# Metro_M4_Express_AirLift.net
KiCad netlist of a schematic drawn in EAGLE
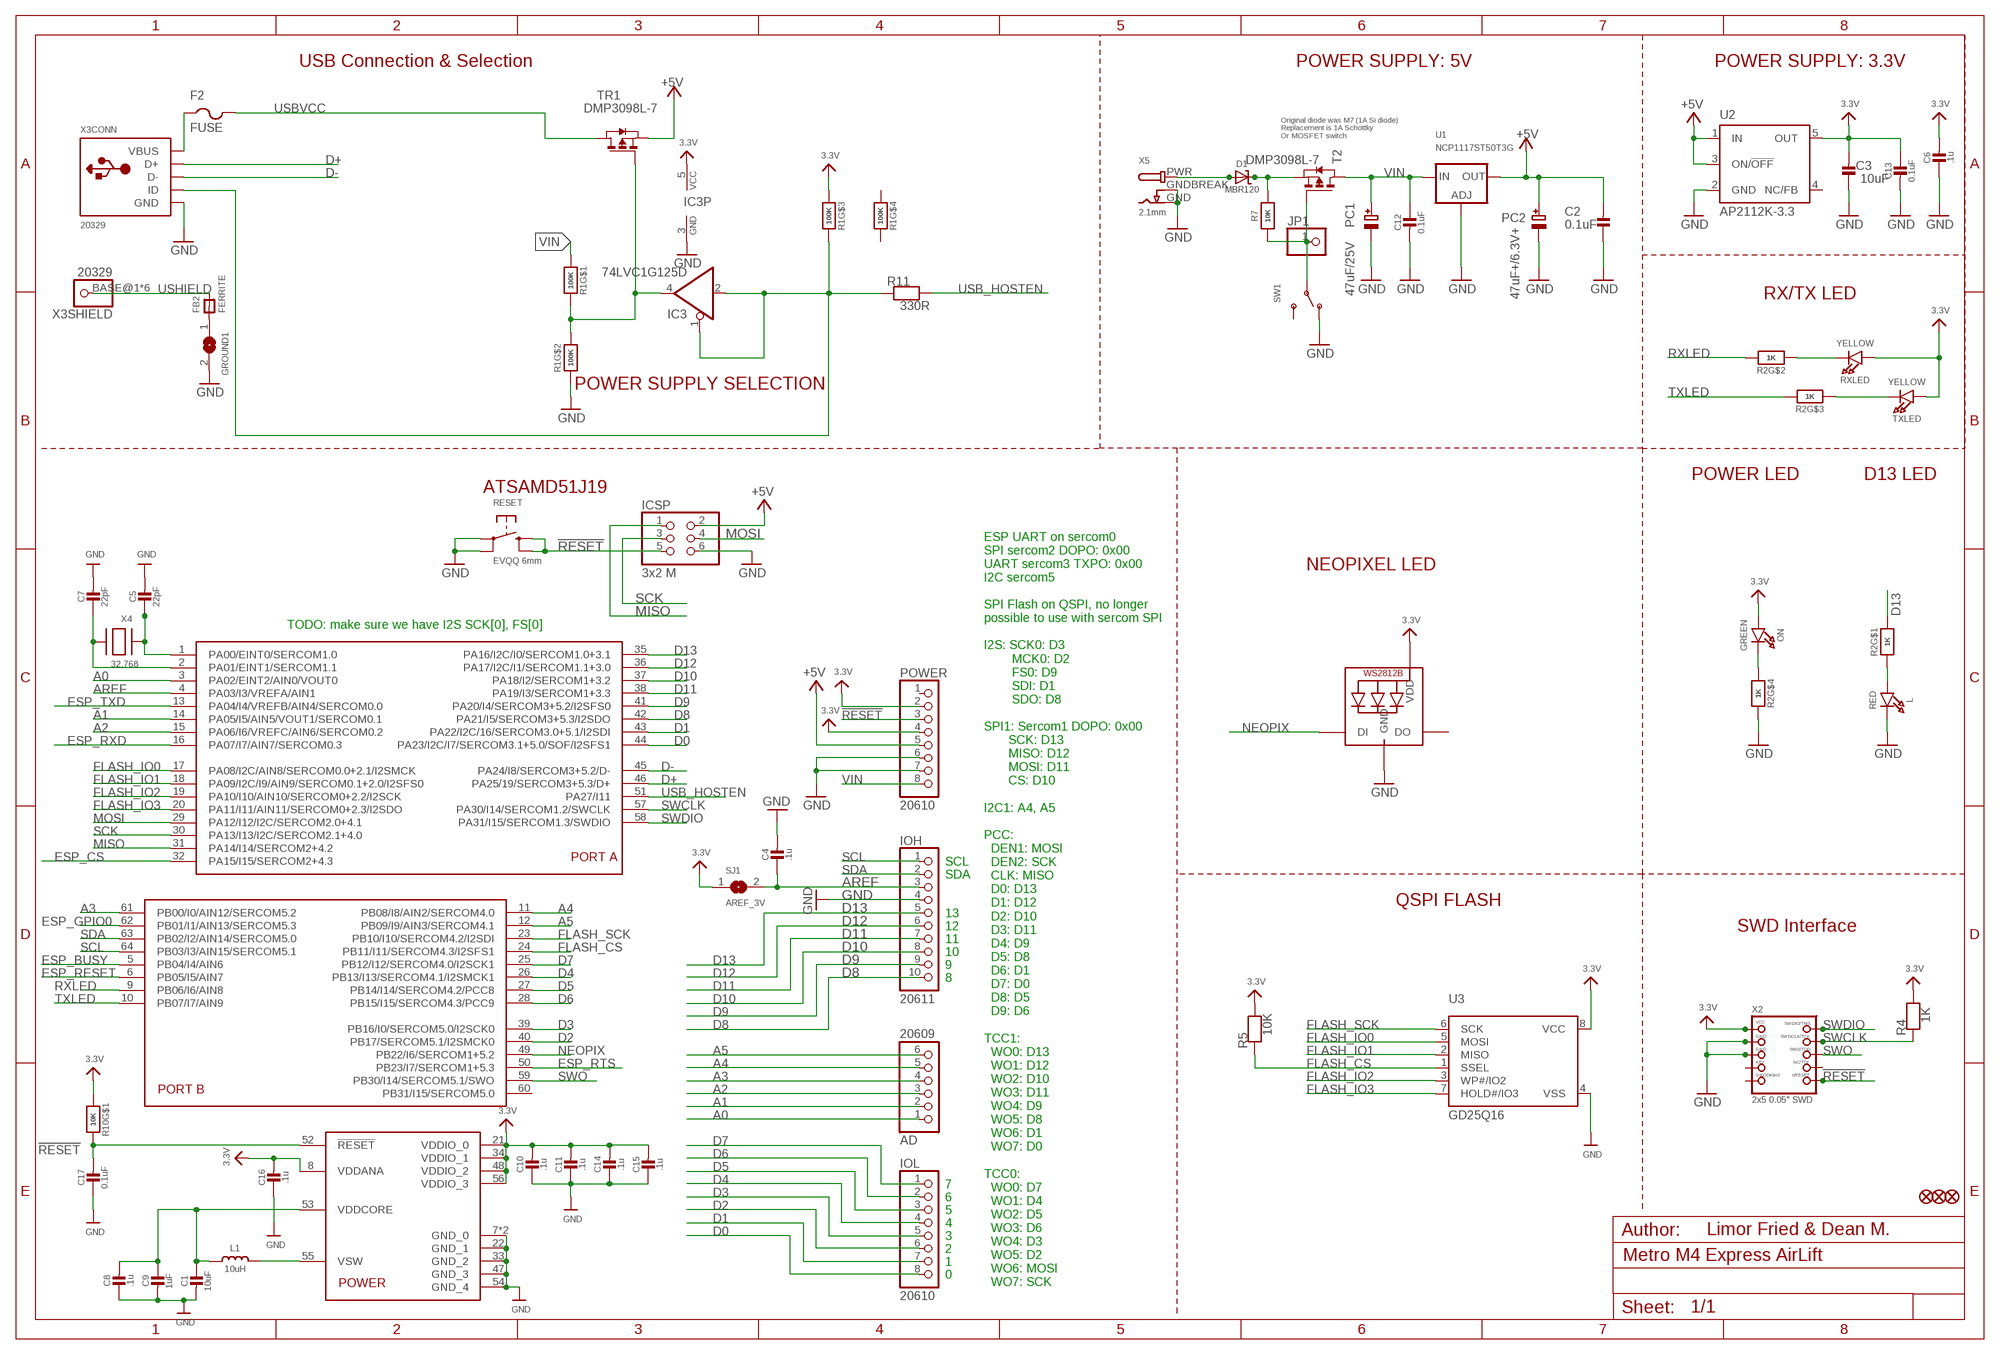
[diagram p0: schematic, sheet 1, part 1 of 2]
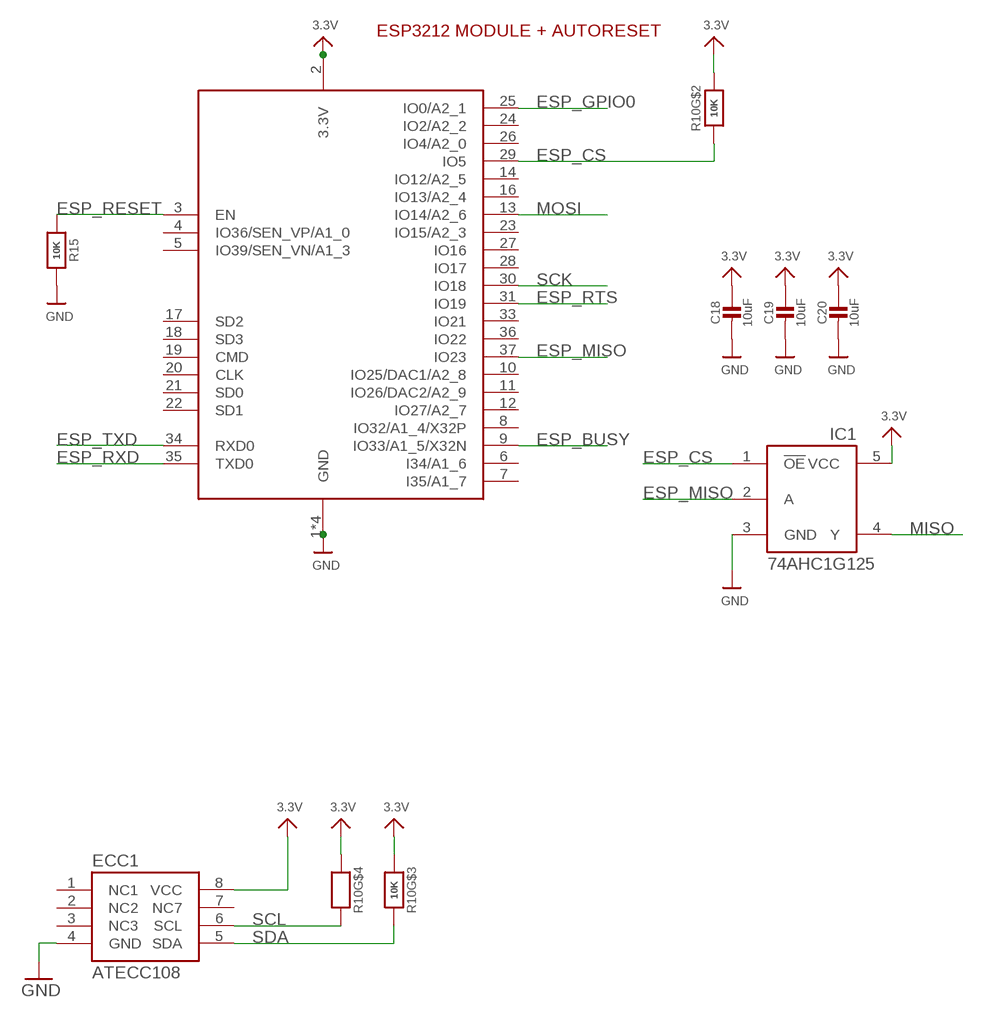
[diagram p1: schematic, sheet 1, part 2 of 2]

(export (version "E")
  (design (tool "Eeschema 10.0.6"))
  (components
    (comp (ref "AD")
      (value "20609")
      (footprint "eagle-import:1X06_OVALWAVE")
      (libsource (lib "eagle-import") (part "HEADER-1X6OVALWAVE"))
    )
    (comp (ref "C1")
      (value "10uF")
      (footprint "eagle-import:0805-NO")
      (libsource (lib "eagle-import") (part "CAP_CERAMIC0805-NOOUTLINE"))
    )
    (comp (ref "C2")
      (value "0.1uF")
      (footprint "eagle-import:0805-NO")
      (libsource (lib "eagle-import") (part "CAP_CERAMIC0805-NOOUTLINE"))
    )
    (comp (ref "C3")
      (value "10uF")
      (footprint "eagle-import:0805-NO")
      (libsource (lib "eagle-import") (part "CAP_CERAMIC0805-NOOUTLINE"))
    )
    (comp (ref "C4")
      (value ".1u")
      (footprint "eagle-import:0603-NO")
      (libsource (lib "eagle-import") (part "CAP_CERAMIC0603_NO"))
    )
    (comp (ref "C5")
      (value "22pF")
      (footprint "eagle-import:0603-NO")
      (libsource (lib "eagle-import") (part "CAP_CERAMIC0603_NO"))
    )
    (comp (ref "C6")
      (value ".1u")
      (footprint "eagle-import:0603-NO")
      (libsource (lib "eagle-import") (part "CAP_CERAMIC0603_NO"))
    )
    (comp (ref "C7")
      (value "22pF")
      (footprint "eagle-import:0603-NO")
      (libsource (lib "eagle-import") (part "CAP_CERAMIC0603_NO"))
    )
    (comp (ref "C8")
      (value ".1u")
      (footprint "eagle-import:0603-NO")
      (libsource (lib "eagle-import") (part "CAP_CERAMIC0603_NO"))
    )
    (comp (ref "C9")
      (value "1uF")
      (footprint "eagle-import:0603-NO")
      (libsource (lib "eagle-import") (part "CAP_CERAMIC0603_NO"))
    )
    (comp (ref "C10")
      (value ".1u")
      (footprint "eagle-import:0603-NO")
      (libsource (lib "eagle-import") (part "CAP_CERAMIC0603_NO"))
    )
    (comp (ref "C11")
      (value ".1u")
      (footprint "eagle-import:0603-NO")
      (libsource (lib "eagle-import") (part "CAP_CERAMIC0603_NO"))
    )
    (comp (ref "C12")
      (value "0.1uF")
      (footprint "eagle-import:0603-NO")
      (libsource (lib "eagle-import") (part "CAP_CERAMIC0603_NO"))
    )
    (comp (ref "C13")
      (value "0.1uF")
      (footprint "eagle-import:0603-NO")
      (libsource (lib "eagle-import") (part "CAP_CERAMIC0603_NO"))
    )
    (comp (ref "C14")
      (value ".1u")
      (footprint "eagle-import:0603-NO")
      (libsource (lib "eagle-import") (part "CAP_CERAMIC0603_NO"))
    )
    (comp (ref "C15")
      (value ".1u")
      (footprint "eagle-import:0603-NO")
      (libsource (lib "eagle-import") (part "CAP_CERAMIC0603_NO"))
    )
    (comp (ref "C16")
      (value ".1u")
      (footprint "eagle-import:0603-NO")
      (libsource (lib "eagle-import") (part "CAP_CERAMIC0603_NO"))
    )
    (comp (ref "C17")
      (value "0.1uF")
      (footprint "eagle-import:0603-NO")
      (libsource (lib "eagle-import") (part "CAP_CERAMIC0603_NO"))
    )
    (comp (ref "C18")
      (value "10uF")
      (footprint "eagle-import:0805-NO")
      (libsource (lib "eagle-import") (part "CAP_CERAMIC0805-NOOUTLINE"))
    )
    (comp (ref "C19")
      (value "10uF")
      (footprint "eagle-import:0805-NO")
      (libsource (lib "eagle-import") (part "CAP_CERAMIC0805-NOOUTLINE"))
    )
    (comp (ref "C20")
      (value "10uF")
      (footprint "eagle-import:0805-NO")
      (libsource (lib "eagle-import") (part "CAP_CERAMIC0805-NOOUTLINE"))
    )
    (comp (ref "D1")
      (value "MBR120")
      (footprint "eagle-import:SOD-123")
      (libsource (lib "eagle-import") (part "DIODE-SCHOTTKYSOD-123"))
    )
    (comp (ref "ECC1")
      (value "ATECC108")
      (footprint "eagle-import:SOIC8")
      (libsource (lib "eagle-import") (part "ATECC108"))
    )
    (comp (ref "F2")
      (value "FUSE")
      (footprint "eagle-import:R1206")
      (libsource (lib "eagle-import") (part "PTCFUSE-1206"))
    )
    (comp (ref "FB2")
      (value "FERRITE")
      (footprint "eagle-import:0805-NO")
      (libsource (lib "eagle-import") (part "FERRITE-0805NO"))
    )
    (comp (ref "FD1")
      (value "FIDUCIAL_1MM")
      (footprint "eagle-import:FIDUCIAL_1MM")
      (libsource (lib "eagle-import") (part "FIDUCIAL_1MM"))
    )
    (comp (ref "FD2")
      (value "FIDUCIAL_1MM")
      (footprint "eagle-import:FIDUCIAL_1MM")
      (libsource (lib "eagle-import") (part "FIDUCIAL_1MM"))
    )
    (comp (ref "FD3")
      (value "FIDUCIAL_1MM")
      (footprint "eagle-import:FIDUCIAL_1MM")
      (libsource (lib "eagle-import") (part "FIDUCIAL_1MM"))
    )
    (comp (ref "GROUND1")
      (value "SOLDERJUMPERCLOSED")
      (footprint "eagle-import:SOLDERJUMPER_CLOSEDWIRE")
      (libsource (lib "eagle-import") (part "SOLDERJUMPERCLOSED"))
    )
    (comp (ref "IC1")
      (value "74AHC1G125")
      (footprint "eagle-import:SOT23-5L")
      (libsource (lib "eagle-import") (part "74AHC1G125"))
    )
    (comp (ref "IC3")
      (value "74LVC1G125D")
      (footprint "eagle-import:SOT23-5")
      (libsource (lib "eagle-import") (part "741G125DBVAHC"))
    )
    (comp (ref "ICSP")
      (value "3x2 M")
      (footprint "eagle-import:2X03_ROUND_70MIL")
      (libsource (lib "eagle-import") (part "HEADER-2X3"))
    )
    (comp (ref "IOH")
      (value "20611")
      (footprint "eagle-import:1X10_OVALWAVE")
      (libsource (lib "eagle-import") (part "HEADER-1X10OVALWAVE"))
    )
    (comp (ref "IOL")
      (value "20610")
      (footprint "eagle-import:1X08_OVALWAVE")
      (libsource (lib "eagle-import") (part "HEADER-1X8OVALWAVE"))
    )
    (comp (ref "JP1")
      (value "HEADER-1X1ROUND")
      (footprint "eagle-import:1X01_ROUND")
      (libsource (lib "eagle-import") (part "HEADER-1X1ROUND"))
    )
    (comp (ref "L")
      (value "RED")
      (footprint "eagle-import:CHIPLED_0805_NOOUTLINE")
      (libsource (lib "eagle-import") (part "LED0805_NOOUTLINE"))
    )
    (comp (ref "L1")
      (value "10uH")
      (footprint "eagle-import:INDUCTOR_1007")
      (libsource (lib "eagle-import") (part "INDUCTOR"))
    )
    (comp (ref "LED1")
      (value "WS2812B3535")
      (footprint "eagle-import:LED3535")
      (libsource (lib "eagle-import") (part "WS2812B3535"))
    )
    (comp (ref "ON")
      (value "GREEN")
      (footprint "eagle-import:CHIPLED_0805_NOOUTLINE")
      (libsource (lib "eagle-import") (part "LED0805_NOOUTLINE"))
    )
    (comp (ref "PC1")
      (value "47uF/25V")
      (footprint "eagle-import:PANASONIC_D")
      (libsource (lib "eagle-import") (part "CAP_ELECTROLYTICPANASONIC_D"))
    )
    (comp (ref "PC2")
      (value "47uF+/6.3V+")
      (footprint "eagle-import:PANASONIC_D")
      (libsource (lib "eagle-import") (part "CAP_ELECTROLYTICPANASONIC_D"))
    )
    (comp (ref "POWER")
      (value "20610")
      (footprint "eagle-import:1X08_OVALWAVE")
      (libsource (lib "eagle-import") (part "HEADER-1X8OVALWAVE"))
    )
    (comp (ref "R1")
      (value "100K")
      (footprint "eagle-import:RESPACK_4X0603")
      (libsource (lib "eagle-import") (part "RESISTOR_4PACK"))
    )
    (comp (ref "R2")
      (value "1K")
      (footprint "eagle-import:RESPACK_4X0603")
      (libsource (lib "eagle-import") (part "RESISTOR_4PACK"))
    )
    (comp (ref "R4")
      (value "1K")
      (footprint "eagle-import:0603-NO")
      (libsource (lib "eagle-import") (part "RESISTOR_0603_NOOUT"))
    )
    (comp (ref "R5")
      (value "10K")
      (footprint "eagle-import:0603-NO")
      (libsource (lib "eagle-import") (part "RESISTOR_0603_NOOUT"))
    )
    (comp (ref "R7")
      (value "10K")
      (footprint "eagle-import:0603-NO")
      (libsource (lib "eagle-import") (part "RESISTOR_0603_NOOUT"))
    )
    (comp (ref "R10")
      (value "10K")
      (footprint "eagle-import:RESPACK_4X0603")
      (libsource (lib "eagle-import") (part "RESISTOR_4PACK"))
    )
    (comp (ref "R11")
      (value "330R")
      (footprint "eagle-import:0603-NO")
      (libsource (lib "eagle-import") (part "RESISTOR_0603_NOOUT"))
    )
    (comp (ref "R15")
      (value "10K")
      (footprint "eagle-import:0603-NO")
      (libsource (lib "eagle-import") (part "RESISTOR_0603_NOOUT"))
    )
    (comp (ref "RESET")
      (value "EVQQ 6mm")
      (footprint "eagle-import:EVQ-Q2_SMALLER")
      (libsource (lib "eagle-import") (part "SWITCH_TACT_SMT_EVQQ2_SMALL"))
    )
    (comp (ref "RXLED")
      (value "YELLOW")
      (footprint "eagle-import:CHIPLED_0805_NOOUTLINE")
      (libsource (lib "eagle-import") (part "LED0805_NOOUTLINE"))
    )
    (comp (ref "SJ1")
      (value "AREF_3V")
      (footprint "eagle-import:SOLDERJUMPER_CLOSEDWIRE")
      (libsource (lib "eagle-import") (part "SOLDERJUMPERCLOSED"))
    )
    (comp (ref "SW1")
      (value "SWITCH_SPDT")
      (footprint "eagle-import:SPDT_SMT_SSSS811101")
      (libsource (lib "eagle-import") (part "SWITCH_SPDT"))
    )
    (comp (ref "T2")
      (value "DMP3098L-7")
      (footprint "eagle-import:SOT-23")
      (libsource (lib "eagle-import") (part "PMOSSOT23"))
    )
    (comp (ref "TR1")
      (value "DMP3098L-7")
      (footprint "eagle-import:SOT-23")
      (fields (field (name "PART_NUMBER") "PMV48XP"))
      (libsource (lib "eagle-import") (part "0297_PMV48XP"))
    )
    (comp (ref "TXLED")
      (value "YELLOW")
      (footprint "eagle-import:CHIPLED_0805_NOOUTLINE")
      (libsource (lib "eagle-import") (part "LED0805_NOOUTLINE"))
    )
    (comp (ref "U$1")
      (value "ATSAMD51J19")
      (footprint "eagle-import:PQFN64-1")
      (libsource (lib "eagle-import") (part "ATSAMD51J"))
    )
    (comp (ref "U1")
      (value "NCP1117ST50T3G")
      (footprint "eagle-import:SOT223-R")
      (libsource (lib "eagle-import") (part "LM1117SOT223-REFLOW"))
    )
    (comp (ref "U2")
      (value "AP2112K-3.3")
      (footprint "eagle-import:SOT23-DBV")
      (libsource (lib "eagle-import") (part "LP2985-XXDBVR33"))
    )
    (comp (ref "U3")
      (value "GD25Q16")
      (footprint "eagle-import:SOIC8_208MIL")
      (libsource (lib "eagle-import") (part "SPIFLASH_8PIN208MIL"))
    )
    (comp (ref "X2")
      (value "2x5 0.05\" SWD")
      (footprint "eagle-import:2X05_1.27MM_BOX_POSTS")
      (libsource (lib "eagle-import") (part "JTAG-CORTEXBOXPOSTS"))
    )
    (comp (ref "X3")
      (value "20329")
      (footprint "eagle-import:4UCONN_20329_V2")
      (libsource (lib "eagle-import") (part "USB_W_SHIELD_V2"))
    )
    (comp (ref "X4")
      (value "32.768")
      (footprint "eagle-import:XTAL3215")
      (libsource (lib "eagle-import") (part "XTAL-3.2X1.5"))
    )
    (comp (ref "X5")
      (value "2.1mm")
      (footprint "eagle-import:DCJACK_2MM_PTH")
      (libsource (lib "eagle-import") (part "DCBARRELPTH"))
    )
    (comp (ref "X6")
      (value "ESP32_WROOM32")
      (footprint "eagle-import:WROOM32")
      (libsource (lib "eagle-import") (part "ESP32_WROOM32"))
    )
  )
  (nets
    (net (code "1") (name "+5V") (class "Default")
      (node (ref "C2") (pin "2") (pinfunction "2_2") (pintype "passive"))
      (node (ref "ICSP") (pin "2") (pinfunction "2_2") (pintype "passive"))
      (node (ref "PC2") (pin "+") (pinfunction "+_+") (pintype "passive"))
      (node (ref "POWER") (pin "5") (pinfunction "5_5") (pintype "passive"))
      (node (ref "TR1") (pin "2") (pinfunction "S_2") (pintype "passive"))
      (node (ref "U1") (pin "2") (pinfunction "OUT_2") (pintype "passive"))
      (node (ref "U1") (pin "4") (pinfunction "OUT_4") (pintype "passive"))
      (node (ref "U2") (pin "1") (pinfunction "IN_1") (pintype "input"))
      (node (ref "U2") (pin "3") (pinfunction "ON/~{OFF}_3") (pintype "input"))
    )
    (net (code "2") (name "/A0") (class "Default")
      (node (ref "AD") (pin "1") (pinfunction "1_1") (pintype "passive"))
      (node (ref "U$1") (pin "3") (pinfunction "PA02/EINT2/AIN0/VOUT0_3") (pintype "bidirectional"))
    )
    (net (code "3") (name "/A1") (class "Default")
      (node (ref "AD") (pin "2") (pinfunction "2_2") (pintype "passive"))
      (node (ref "U$1") (pin "14") (pinfunction "PA05/I5/AIN5/VOUT1/SERCOM0.1_14") (pintype "bidirectional"))
    )
    (net (code "4") (name "/A2") (class "Default")
      (node (ref "AD") (pin "3") (pinfunction "3_3") (pintype "passive"))
      (node (ref "U$1") (pin "15") (pinfunction "PA06/I6/VREFC/AIN6/SERCOM0.2_15") (pintype "bidirectional"))
    )
    (net (code "5") (name "/A3") (class "Default")
      (node (ref "AD") (pin "4") (pinfunction "4_4") (pintype "passive"))
      (node (ref "U$1") (pin "61") (pinfunction "PB00/I0/AIN12/SERCOM5.2_61") (pintype "bidirectional"))
    )
    (net (code "6") (name "/A4") (class "Default")
      (node (ref "AD") (pin "5") (pinfunction "5_5") (pintype "passive"))
      (node (ref "U$1") (pin "11") (pinfunction "PB08/I8/AIN2/SERCOM4.0_11") (pintype "bidirectional"))
    )
    (net (code "7") (name "/A5") (class "Default")
      (node (ref "AD") (pin "6") (pinfunction "6_6") (pintype "passive"))
      (node (ref "U$1") (pin "12") (pinfunction "PB09/I9/AIN3/SERCOM4.1_12") (pintype "bidirectional"))
    )
    (net (code "8") (name "/AREF") (class "Default")
      (node (ref "C4") (pin "1") (pinfunction "1_1") (pintype "passive"))
      (node (ref "IOH") (pin "3") (pinfunction "3_3") (pintype "passive"))
      (node (ref "SJ1") (pin "2") (pinfunction "2_2") (pintype "passive"))
      (node (ref "U$1") (pin "4") (pinfunction "PA03/I3/VREFA/AIN1_4") (pintype "bidirectional"))
    )
    (net (code "9") (name "/D+") (class "Default")
      (node (ref "U$1") (pin "46") (pinfunction "PA25/19/SERCOM3+5.3/D+_46") (pintype "bidirectional"))
      (node (ref "X3") (pin "D+") (pinfunction "D+_D+") (pintype "bidirectional"))
    )
    (net (code "10") (name "/D-") (class "Default")
      (node (ref "U$1") (pin "45") (pinfunction "PA24/I8/SERCOM3+5.2/D-_45") (pintype "bidirectional"))
      (node (ref "X3") (pin "D-") (pinfunction "D-_D-") (pintype "bidirectional"))
    )
    (net (code "11") (name "/D0") (class "Default")
      (node (ref "IOL") (pin "8") (pinfunction "8_8") (pintype "passive"))
      (node (ref "U$1") (pin "44") (pinfunction "PA23/I2C/I7/SERCOM3.1+5.0/SOF/I2SFS1_44") (pintype "bidirectional"))
    )
    (net (code "12") (name "/D1") (class "Default")
      (node (ref "IOL") (pin "7") (pinfunction "7_7") (pintype "passive"))
      (node (ref "U$1") (pin "43") (pinfunction "PA22/I2C/16/SERCOM3.0+5.1/I2SDI_43") (pintype "bidirectional"))
    )
    (net (code "13") (name "/D2") (class "Default")
      (node (ref "IOL") (pin "6") (pinfunction "6_6") (pintype "passive"))
      (node (ref "U$1") (pin "40") (pinfunction "PB17/SERCOM5.1/I2SMCK0_40") (pintype "bidirectional"))
    )
    (net (code "14") (name "/D3") (class "Default")
      (node (ref "IOL") (pin "5") (pinfunction "5_5") (pintype "passive"))
      (node (ref "U$1") (pin "39") (pinfunction "PB16/I0/SERCOM5.0/I2SCK0_39") (pintype "bidirectional"))
    )
    (net (code "15") (name "/D4") (class "Default")
      (node (ref "IOL") (pin "4") (pinfunction "4_4") (pintype "passive"))
      (node (ref "U$1") (pin "26") (pinfunction "PB13/I13/SERCOM4.1/I2SMCK1_26") (pintype "bidirectional"))
    )
    (net (code "16") (name "/D5") (class "Default")
      (node (ref "IOL") (pin "3") (pinfunction "3_3") (pintype "passive"))
      (node (ref "U$1") (pin "27") (pinfunction "PB14/I14/SERCOM4.2/PCC8_27") (pintype "bidirectional"))
    )
    (net (code "17") (name "/D6") (class "Default")
      (node (ref "IOL") (pin "2") (pinfunction "2_2") (pintype "passive"))
      (node (ref "U$1") (pin "28") (pinfunction "PB15/I15/SERCOM4.3/PCC9_28") (pintype "bidirectional"))
    )
    (net (code "18") (name "/D7") (class "Default")
      (node (ref "IOL") (pin "1") (pinfunction "1_1") (pintype "passive"))
      (node (ref "U$1") (pin "25") (pinfunction "PB12/I12/SERCOM4.0/I2SCK1_25") (pintype "bidirectional"))
    )
    (net (code "19") (name "/D8") (class "Default")
      (node (ref "IOH") (pin "10") (pinfunction "10_10") (pintype "passive"))
      (node (ref "U$1") (pin "42") (pinfunction "PA21/I5/SERCOM3+5.3/I2SDO_42") (pintype "bidirectional"))
    )
    (net (code "20") (name "/D9") (class "Default")
      (node (ref "IOH") (pin "9") (pinfunction "9_9") (pintype "passive"))
      (node (ref "U$1") (pin "41") (pinfunction "PA20/I4/SERCOM3+5.2/I2SFS0_41") (pintype "bidirectional"))
    )
    (net (code "21") (name "/D10") (class "Default")
      (node (ref "IOH") (pin "8") (pinfunction "8_8") (pintype "passive"))
      (node (ref "U$1") (pin "37") (pinfunction "PA18/I2/SERCOM1+3.2_37") (pintype "bidirectional"))
    )
    (net (code "22") (name "/D11") (class "Default")
      (node (ref "IOH") (pin "7") (pinfunction "7_7") (pintype "passive"))
      (node (ref "U$1") (pin "38") (pinfunction "PA19/I3/SERCOM1+3.3_38") (pintype "bidirectional"))
    )
    (net (code "23") (name "/D12") (class "Default")
      (node (ref "IOH") (pin "6") (pinfunction "6_6") (pintype "passive"))
      (node (ref "U$1") (pin "36") (pinfunction "PA17/I2C/I1/SERCOM1.1+3.0_36") (pintype "bidirectional"))
    )
    (net (code "24") (name "/D13") (class "Default")
      (node (ref "IOH") (pin "5") (pinfunction "5_5") (pintype "passive"))
      (node (ref "R2") (pin "8") (pinfunction "2_8") (pintype "passive"))
      (node (ref "U$1") (pin "35") (pinfunction "PA16/I2C/I0/SERCOM1.0+3.1_35") (pintype "bidirectional"))
    )
    (net (code "25") (name "/ESP_BUSY") (class "Default")
      (node (ref "U$1") (pin "5") (pinfunction "PB04/I4/AIN6_5") (pintype "bidirectional"))
      (node (ref "X6") (pin "9") (pinfunction "IO33/A1_5/X32N_9") (pintype "bidirectional"))
    )
    (net (code "26") (name "/ESP_CS") (class "Default")
      (node (ref "IC1") (pin "1") (pinfunction "~{OE}_1") (pintype "input"))
      (node (ref "R10") (pin "2") (pinfunction "1_2") (pintype "passive"))
      (node (ref "U$1") (pin "32") (pinfunction "PA15/I15/SERCOM2+4.3_32") (pintype "bidirectional"))
      (node (ref "X6") (pin "29") (pinfunction "IO5_29") (pintype "bidirectional"))
    )
    (net (code "27") (name "/ESP_GPIO0") (class "Default")
      (node (ref "U$1") (pin "62") (pinfunction "PB01/I1/AIN13/SERCOM5.3_62") (pintype "bidirectional"))
      (node (ref "X6") (pin "25") (pinfunction "IO0/A2_1_25") (pintype "bidirectional"))
    )
    (net (code "28") (name "/ESP_MISO") (class "Default")
      (node (ref "IC1") (pin "2") (pinfunction "A_2") (pintype "input"))
      (node (ref "X6") (pin "37") (pinfunction "IO23_37") (pintype "bidirectional"))
    )
    (net (code "29") (name "/ESP_RESET") (class "Default")
      (node (ref "R15") (pin "1") (pinfunction "1_1") (pintype "passive"))
      (node (ref "U$1") (pin "6") (pinfunction "PB05/I5/AIN7_6") (pintype "bidirectional"))
      (node (ref "X6") (pin "3") (pinfunction "EN_3") (pintype "input"))
    )
    (net (code "30") (name "/ESP_RTS") (class "Default")
      (node (ref "U$1") (pin "50") (pinfunction "PB23/I7/SERCOM1+5.3_50") (pintype "bidirectional"))
      (node (ref "X6") (pin "31") (pinfunction "IO19_31") (pintype "bidirectional"))
    )
    (net (code "31") (name "/ESP_RXD") (class "Default")
      (node (ref "U$1") (pin "16") (pinfunction "PA07/I7/AIN7/SERCOM0.3_16") (pintype "bidirectional"))
      (node (ref "X6") (pin "35") (pinfunction "TXD0_35") (pintype "output"))
    )
    (net (code "32") (name "/ESP_TXD") (class "Default")
      (node (ref "U$1") (pin "13") (pinfunction "PA04/I4/VREFB/AIN4/SERCOM0.0_13") (pintype "bidirectional"))
      (node (ref "X6") (pin "34") (pinfunction "RXD0_34") (pintype "input"))
    )
    (net (code "33") (name "/FLASH_CS") (class "Default")
      (node (ref "R5") (pin "1") (pinfunction "1_1") (pintype "passive"))
      (node (ref "U$1") (pin "24") (pinfunction "PB11/I11/SERCOM4.3/I2SFS1_24") (pintype "bidirectional"))
      (node (ref "U3") (pin "1") (pinfunction "SSEL_1") (pintype "bidirectional"))
    )
    (net (code "34") (name "/FLASH_IO0") (class "Default")
      (node (ref "U$1") (pin "17") (pinfunction "PA08/I2C/AIN8/SERCOM0.0+2.1/I2SMCK_17") (pintype "bidirectional"))
      (node (ref "U3") (pin "5") (pinfunction "MOSI_5") (pintype "bidirectional"))
    )
    (net (code "35") (name "/FLASH_IO1") (class "Default")
      (node (ref "U$1") (pin "18") (pinfunction "PA09/I2C/I9/AIN9/SERCOM0.1+2.0/I2SFS0_18") (pintype "bidirectional"))
      (node (ref "U3") (pin "2") (pinfunction "MISO_2") (pintype "bidirectional"))
    )
    (net (code "36") (name "/FLASH_IO2") (class "Default")
      (node (ref "U$1") (pin "19") (pinfunction "PA10/I10/AIN10/SERCOM0+2.2/I2SCK_19") (pintype "bidirectional"))
      (node (ref "U3") (pin "3") (pinfunction "WP#/IO2_3") (pintype "bidirectional"))
    )
    (net (code "37") (name "/FLASH_IO3") (class "Default")
      (node (ref "U$1") (pin "20") (pinfunction "PA11/I11/AIN11/SERCOM0+2.3/I2SDO_20") (pintype "bidirectional"))
      (node (ref "U3") (pin "7") (pinfunction "HOLD#/IO3_7") (pintype "bidirectional"))
    )
    (net (code "38") (name "/FLASH_SCK") (class "Default")
      (node (ref "U$1") (pin "23") (pinfunction "PB10/I10/SERCOM4.2/I2SDI_23") (pintype "bidirectional"))
      (node (ref "U3") (pin "6") (pinfunction "SCK_6") (pintype "bidirectional"))
    )
    (net (code "39") (name "/MISO") (class "Default")
      (node (ref "IC1") (pin "4") (pinfunction "Y_4") (pintype "output"))
      (node (ref "ICSP") (pin "1") (pinfunction "1_1") (pintype "passive"))
      (node (ref "U$1") (pin "31") (pinfunction "PA14/I14/SERCOM2+4.2_31") (pintype "bidirectional"))
    )
    (net (code "40") (name "/MOSI") (class "Default")
      (node (ref "ICSP") (pin "4") (pinfunction "4_4") (pintype "passive"))
      (node (ref "U$1") (pin "29") (pinfunction "PA12/I12/I2C/SERCOM2.0+4.1_29") (pintype "bidirectional"))
      (node (ref "X6") (pin "13") (pinfunction "IO14/A2_6_13") (pintype "bidirectional"))
    )
    (net (code "41") (name "/NEOPIX") (class "Default")
      (node (ref "LED1") (pin "1") (pinfunction "DI_1") (pintype "input"))
      (node (ref "U$1") (pin "49") (pinfunction "PB22/I6/SERCOM1+5.2_49") (pintype "bidirectional"))
    )
    (net (code "42") (name "/RXLED") (class "Default")
      (node (ref "R2") (pin "7") (pinfunction "2_7") (pintype "passive"))
      (node (ref "U$1") (pin "9") (pinfunction "PB06/I6/AIN8_9") (pintype "bidirectional"))
    )
    (net (code "43") (name "/SCK") (class "Default")
      (node (ref "ICSP") (pin "3") (pinfunction "3_3") (pintype "passive"))
      (node (ref "U$1") (pin "30") (pinfunction "PA13/I13/I2C/SERCOM2.1+4.0_30") (pintype "bidirectional"))
      (node (ref "X6") (pin "30") (pinfunction "IO18_30") (pintype "bidirectional"))
    )
    (net (code "44") (name "/SCL") (class "Default")
      (node (ref "ECC1") (pin "6") (pinfunction "SCL_6") (pintype "bidirectional"))
      (node (ref "IOH") (pin "1") (pinfunction "1_1") (pintype "passive"))
      (node (ref "R10") (pin "5") (pinfunction "2_5") (pintype "passive"))
      (node (ref "U$1") (pin "64") (pinfunction "PB03/I3/AIN15/SERCOM5.1_64") (pintype "bidirectional"))
    )
    (net (code "45") (name "/SDA") (class "Default")
      (node (ref "ECC1") (pin "5") (pinfunction "SDA_5") (pintype "bidirectional"))
      (node (ref "IOH") (pin "2") (pinfunction "2_2") (pintype "passive"))
      (node (ref "R10") (pin "6") (pinfunction "2_6") (pintype "passive"))
      (node (ref "U$1") (pin "63") (pinfunction "PB02/I2/AIN14/SERCOM5.0_63") (pintype "bidirectional"))
    )
    (net (code "46") (name "/SWCLK") (class "Default")
      (node (ref "R4") (pin "1") (pinfunction "1_1") (pintype "passive"))
      (node (ref "U$1") (pin "57") (pinfunction "PA30/I14/SERCOM1.2/SWCLK_57") (pintype "bidirectional"))
      (node (ref "X2") (pin "4") (pinfunction "SWDCLK_4") (pintype "bidirectional"))
    )
    (net (code "47") (name "/SWDIO") (class "Default")
      (node (ref "U$1") (pin "58") (pinfunction "PA31/I15/SERCOM1.3/SWDIO_58") (pintype "bidirectional"))
      (node (ref "X2") (pin "2") (pinfunction "SWDIO_2") (pintype "bidirectional"))
    )
    (net (code "48") (name "/SWO") (class "Default")
      (node (ref "U$1") (pin "59") (pinfunction "PB30/I14/SERCOM5.1/SWO_59") (pintype "bidirectional"))
      (node (ref "X2") (pin "6") (pinfunction "SWO_6") (pintype "bidirectional"))
    )
    (net (code "49") (name "/TXLED") (class "Default")
      (node (ref "R2") (pin "6") (pinfunction "2_6") (pintype "passive"))
      (node (ref "U$1") (pin "10") (pinfunction "PB07/I7/AIN9_10") (pintype "bidirectional"))
    )
    (net (code "50") (name "/USBVCC") (class "Default")
      (node (ref "F2") (pin "2") (pinfunction "2_2") (pintype "passive"))
      (node (ref "TR1") (pin "1") (pinfunction "D_1") (pintype "passive"))
    )
    (net (code "51") (name "/USB_HOSTEN") (class "Default")
      (node (ref "R11") (pin "2") (pinfunction "2_2") (pintype "passive"))
      (node (ref "U$1") (pin "51") (pinfunction "PA27/I11_51") (pintype "bidirectional"))
    )
    (net (code "52") (name "/USHIELD") (class "Default")
      (node (ref "FB2") (pin "2") (pinfunction "P$2_2") (pintype "passive"))
      (node (ref "X3") (pin "BASE@1") (pinfunction "1_BASE@1") (pintype "passive"))
      (node (ref "X3") (pin "BASE@2") (pinfunction "1_BASE@2") (pintype "passive"))
      (node (ref "X3") (pin "SPRT@1") (pinfunction "1_SPRT@1") (pintype "passive"))
      (node (ref "X3") (pin "SPRT@2") (pinfunction "1_SPRT@2") (pintype "passive"))
      (node (ref "X3") (pin "SPRT@3") (pinfunction "1_SPRT@3") (pintype "passive"))
      (node (ref "X3") (pin "SPRT@4") (pinfunction "1_SPRT@4") (pintype "passive"))
    )
    (net (code "53") (name "/~{RESET}") (class "Default")
      (node (ref "C17") (pin "2") (pinfunction "2_2") (pintype "passive"))
      (node (ref "ICSP") (pin "5") (pinfunction "5_5") (pintype "passive"))
      (node (ref "POWER") (pin "3") (pinfunction "3_3") (pintype "passive"))
      (node (ref "R10") (pin "8") (pinfunction "2_8") (pintype "passive"))
      (node (ref "RESET") (pin "B") (pinfunction "S_B") (pintype "passive"))
      (node (ref "RESET") (pin "B'") (pinfunction "S1_B'") (pintype "passive"))
      (node (ref "U$1") (pin "52") (pinfunction "~{RESET}_52") (pintype "bidirectional"))
      (node (ref "X2") (pin "10") (pinfunction "NRESET_10") (pintype "bidirectional"))
    )
    (net (code "54") (name "3.3V") (class "Default")
      (node (ref "C10") (pin "2") (pinfunction "2_2") (pintype "passive"))
      (node (ref "C11") (pin "2") (pinfunction "2_2") (pintype "passive"))
      (node (ref "C13") (pin "1") (pinfunction "1_1") (pintype "passive"))
      (node (ref "C14") (pin "2") (pinfunction "2_2") (pintype "passive"))
      (node (ref "C15") (pin "2") (pinfunction "2_2") (pintype "passive"))
      (node (ref "C16") (pin "2") (pinfunction "2_2") (pintype "passive"))
      (node (ref "C18") (pin "1") (pinfunction "1_1") (pintype "passive"))
      (node (ref "C19") (pin "1") (pinfunction "1_1") (pintype "passive"))
      (node (ref "C20") (pin "1") (pinfunction "1_1") (pintype "passive"))
      (node (ref "C3") (pin "2") (pinfunction "2_2") (pintype "passive"))
      (node (ref "C6") (pin "2") (pinfunction "2_2") (pintype "passive"))
      (node (ref "ECC1") (pin "8") (pinfunction "VCC_8") (pintype "power_in"))
      (node (ref "IC1") (pin "5") (pinfunction "VCC_5") (pintype "power_in"))
      (node (ref "IC3") (pin "5") (pinfunction "VCC_5") (pintype "power_in"))
      (node (ref "LED1") (pin "2") (pinfunction "VDD_2") (pintype "power_in"))
      (node (ref "ON") (pin "A") (pinfunction "A_A") (pintype "passive"))
      (node (ref "POWER") (pin "2") (pinfunction "2_2") (pintype "passive"))
      (node (ref "POWER") (pin "4") (pinfunction "4_4") (pintype "passive"))
      (node (ref "R1") (pin "3") (pinfunction "1_3") (pintype "passive"))
      (node (ref "R10") (pin "1") (pinfunction "1_1") (pintype "passive"))
      (node (ref "R10") (pin "3") (pinfunction "1_3") (pintype "passive"))
      (node (ref "R10") (pin "4") (pinfunction "1_4") (pintype "passive"))
      (node (ref "R10") (pin "7") (pinfunction "2_7") (pintype "passive"))
      (node (ref "R4") (pin "2") (pinfunction "2_2") (pintype "passive"))
      (node (ref "R5") (pin "2") (pinfunction "2_2") (pintype "passive"))
      (node (ref "RXLED") (pin "A") (pinfunction "A_A") (pintype "passive"))
      (node (ref "SJ1") (pin "1") (pinfunction "1_1") (pintype "passive"))
      (node (ref "TXLED") (pin "A") (pinfunction "A_A") (pintype "passive"))
      (node (ref "U$1") (pin "21") (pinfunction "VDDIO_0_21") (pintype "bidirectional"))
      (node (ref "U$1") (pin "34") (pinfunction "VDDIO_1_34") (pintype "bidirectional"))
      (node (ref "U$1") (pin "48") (pinfunction "VDDIO_2_48") (pintype "bidirectional"))
      (node (ref "U$1") (pin "56") (pinfunction "VDDIO_3_56") (pintype "bidirectional"))
      (node (ref "U$1") (pin "8") (pinfunction "VDDANA_8") (pintype "bidirectional"))
      (node (ref "U2") (pin "5") (pinfunction "OUT_5") (pintype "passive"))
      (node (ref "U3") (pin "8") (pinfunction "VCC_8") (pintype "bidirectional"))
      (node (ref "X2") (pin "1") (pinfunction "VCC_1") (pintype "power_in"))
      (node (ref "X6") (pin "2") (pinfunction "3.3V_2") (pintype "passive"))
    )
    (net (code "55") (name "GND") (class "Default")
      (node (ref "C1") (pin "2") (pinfunction "2_2") (pintype "passive"))
      (node (ref "C10") (pin "1") (pinfunction "1_1") (pintype "passive"))
      (node (ref "C11") (pin "1") (pinfunction "1_1") (pintype "passive"))
      (node (ref "C12") (pin "2") (pinfunction "2_2") (pintype "passive"))
      (node (ref "C13") (pin "2") (pinfunction "2_2") (pintype "passive"))
      (node (ref "C14") (pin "1") (pinfunction "1_1") (pintype "passive"))
      (node (ref "C15") (pin "1") (pinfunction "1_1") (pintype "passive"))
      (node (ref "C16") (pin "1") (pinfunction "1_1") (pintype "passive"))
      (node (ref "C17") (pin "1") (pinfunction "1_1") (pintype "passive"))
      (node (ref "C18") (pin "2") (pinfunction "2_2") (pintype "passive"))
      (node (ref "C19") (pin "2") (pinfunction "2_2") (pintype "passive"))
      (node (ref "C2") (pin "1") (pinfunction "1_1") (pintype "passive"))
      (node (ref "C20") (pin "2") (pinfunction "2_2") (pintype "passive"))
      (node (ref "C3") (pin "1") (pinfunction "1_1") (pintype "passive"))
      (node (ref "C4") (pin "2") (pinfunction "2_2") (pintype "passive"))
      (node (ref "C5") (pin "2") (pinfunction "2_2") (pintype "passive"))
      (node (ref "C6") (pin "1") (pinfunction "1_1") (pintype "passive"))
      (node (ref "C7") (pin "2") (pinfunction "2_2") (pintype "passive"))
      (node (ref "C8") (pin "1") (pinfunction "1_1") (pintype "passive"))
      (node (ref "C9") (pin "2") (pinfunction "2_2") (pintype "passive"))
      (node (ref "ECC1") (pin "4") (pinfunction "GND_4") (pintype "power_in"))
      (node (ref "GROUND1") (pin "2") (pinfunction "2_2") (pintype "passive"))
      (node (ref "IC1") (pin "3") (pinfunction "GND_3") (pintype "power_in"))
      (node (ref "IC3") (pin "3") (pinfunction "GND_3") (pintype "power_in"))
      (node (ref "ICSP") (pin "6") (pinfunction "6_6") (pintype "passive"))
      (node (ref "IOH") (pin "4") (pinfunction "4_4") (pintype "passive"))
      (node (ref "L") (pin "C") (pinfunction "C_C") (pintype "passive"))
      (node (ref "LED1") (pin "4") (pinfunction "GND_4") (pintype "power_in"))
      (node (ref "PC1") (pin "-") (pinfunction "-_-") (pintype "passive"))
      (node (ref "PC2") (pin "-") (pinfunction "-_-") (pintype "passive"))
      (node (ref "POWER") (pin "6") (pinfunction "6_6") (pintype "passive"))
      (node (ref "POWER") (pin "7") (pinfunction "7_7") (pintype "passive"))
      (node (ref "R1") (pin "2") (pinfunction "1_2") (pintype "passive"))
      (node (ref "R15") (pin "2") (pinfunction "2_2") (pintype "passive"))
      (node (ref "R2") (pin "5") (pinfunction "2_5") (pintype "passive"))
      (node (ref "RESET") (pin "A") (pinfunction "P_A") (pintype "passive"))
      (node (ref "RESET") (pin "A'") (pinfunction "P1_A'") (pintype "passive"))
      (node (ref "SW1") (pin "A") (pinfunction "O_A") (pintype "passive"))
      (node (ref "U$1") (pin "22") (pinfunction "GND_1_22") (pintype "bidirectional"))
      (node (ref "U$1") (pin "33") (pinfunction "GND_2_33") (pintype "bidirectional"))
      (node (ref "U$1") (pin "47") (pinfunction "GND_3_47") (pintype "bidirectional"))
      (node (ref "U$1") (pin "54") (pinfunction "GND_4_54") (pintype "bidirectional"))
      (node (ref "U$1") (pin "7") (pinfunction "GND_0_7") (pintype "bidirectional"))
      (node (ref "U$1") (pin "EXP") (pinfunction "GND_0_EXP") (pintype "bidirectional"))
      (node (ref "U1") (pin "1") (pinfunction "ADJ_1") (pintype "input"))
      (node (ref "U2") (pin "2") (pinfunction "GND_2") (pintype "power_in"))
      (node (ref "U3") (pin "4") (pinfunction "VSS_4") (pintype "bidirectional"))
      (node (ref "X2") (pin "3") (pinfunction "GND_3") (pintype "power_in"))
      (node (ref "X2") (pin "5") (pinfunction "GND_5") (pintype "power_in"))
      (node (ref "X3") (pin "GND") (pinfunction "GND_GND") (pintype "power_in"))
      (node (ref "X5") (pin "GND") (pinfunction "GND_GND") (pintype "power_in"))
      (node (ref "X5") (pin "GNDBREAK") (pinfunction "GNDBREAK_GNDBREAK") (pintype "power_in"))
      (node (ref "X6") (pin "1") (pinfunction "GND_1") (pintype "passive"))
      (node (ref "X6") (pin "15") (pinfunction "GND_15") (pintype "passive"))
      (node (ref "X6") (pin "38") (pinfunction "GND_38") (pintype "passive"))
      (node (ref "X6") (pin "P$1") (pinfunction "GND_P$1") (pintype "passive"))
    )
    (net (code "56") (name "Net-(D1-PadA)") (class "Default")
      (node (ref "D1") (pin "A") (pinfunction "A_A") (pintype "passive"))
      (node (ref "X5") (pin "PWR") (pinfunction "PWR_PWR") (pintype "power_in"))
    )
    (net (code "57") (name "Net-(F2-Pad1)") (class "Default")
      (node (ref "F2") (pin "1") (pinfunction "1_1") (pintype "passive"))
      (node (ref "X3") (pin "VBUS") (pinfunction "VBUS_VBUS") (pintype "power_in"))
    )
    (net (code "58") (name "Net-(FB2-P$1)") (class "Default")
      (node (ref "FB2") (pin "1") (pinfunction "P$1_1") (pintype "passive"))
      (node (ref "GROUND1") (pin "1") (pinfunction "1_1") (pintype "passive"))
    )
    (net (code "59") (name "Net-(IC3A-I)") (class "Default")
      (node (ref "IC3") (pin "1") (pinfunction "OE_1") (pintype "input"))
      (node (ref "IC3") (pin "2") (pinfunction "I_2") (pintype "input"))
      (node (ref "R1") (pin "6") (pinfunction "2_6") (pintype "passive"))
      (node (ref "R11") (pin "1") (pinfunction "1_1") (pintype "passive"))
      (node (ref "X3") (pin "ID") (pinfunction "ID_ID") (pintype "bidirectional"))
    )
    (net (code "60") (name "Net-(IC3A-O)") (class "Default")
      (node (ref "IC3") (pin "4") (pinfunction "O_4") (pintype "tri_state"))
      (node (ref "R1") (pin "7") (pinfunction "2_7") (pintype "passive"))
      (node (ref "R1") (pin "8") (pinfunction "2_8") (pintype "passive"))
      (node (ref "TR1") (pin "3") (pinfunction "G_3") (pintype "passive"))
    )
    (net (code "61") (name "Net-(L-PadA)") (class "Default")
      (node (ref "L") (pin "A") (pinfunction "A_A") (pintype "passive"))
      (node (ref "R2") (pin "1") (pinfunction "1_1") (pintype "passive"))
    )
    (net (code "62") (name "Net-(L1-1)") (class "Default")
      (node (ref "C1") (pin "1") (pinfunction "1_1") (pintype "passive"))
      (node (ref "C8") (pin "2") (pinfunction "2_2") (pintype "passive"))
      (node (ref "C9") (pin "1") (pinfunction "1_1") (pintype "passive"))
      (node (ref "L1") (pin "P$1") (pinfunction "1_P$1") (pintype "passive"))
      (node (ref "U$1") (pin "53") (pinfunction "VDDCORE_53") (pintype "bidirectional"))
    )
    (net (code "63") (name "Net-(L1-2)") (class "Default")
      (node (ref "L1") (pin "P$2") (pinfunction "2_P$2") (pintype "passive"))
      (node (ref "U$1") (pin "55") (pinfunction "VSW_55") (pintype "bidirectional"))
    )
    (net (code "64") (name "Net-(R2B-1)") (class "Default")
      (node (ref "R2") (pin "2") (pinfunction "1_2") (pintype "passive"))
      (node (ref "RXLED") (pin "C") (pinfunction "C_C") (pintype "passive"))
    )
    (net (code "65") (name "Net-(R2C-1)") (class "Default")
      (node (ref "R2") (pin "3") (pinfunction "1_3") (pintype "passive"))
      (node (ref "TXLED") (pin "C") (pinfunction "C_C") (pintype "passive"))
    )
    (net (code "66") (name "Net-(R2D-1)") (class "Default")
      (node (ref "ON") (pin "C") (pinfunction "C_C") (pintype "passive"))
      (node (ref "R2") (pin "4") (pinfunction "1_4") (pintype "passive"))
    )
    (net (code "67") (name "Net-(SW1-P)") (class "Default")
      (node (ref "JP1") (pin "1") (pinfunction "1_1") (pintype "passive"))
      (node (ref "R7") (pin "1") (pinfunction "1_1") (pintype "passive"))
      (node (ref "SW1") (pin "B") (pinfunction "P_B") (pintype "passive"))
      (node (ref "T2") (pin "3") (pinfunction "G_3") (pintype "passive"))
    )
    (net (code "68") (name "Net-(T2-S)") (class "Default")
      (node (ref "D1") (pin "C") (pinfunction "C_C") (pintype "passive"))
      (node (ref "R7") (pin "2") (pinfunction "2_2") (pintype "passive"))
      (node (ref "T2") (pin "2") (pinfunction "S_2") (pintype "passive"))
    )
    (net (code "69") (name "Net-(U$1A-PA00{slash}EINT0{slash}SERCOM1.0)") (class "Default")
      (node (ref "C5") (pin "1") (pinfunction "1_1") (pintype "passive"))
      (node (ref "U$1") (pin "1") (pinfunction "PA00/EINT0/SERCOM1.0_1") (pintype "bidirectional"))
      (node (ref "X4") (pin "P$1") (pinfunction "P$1_P$1") (pintype "bidirectional"))
    )
    (net (code "70") (name "Net-(U$1A-PA01{slash}EINT1{slash}SERCOM1.1)") (class "Default")
      (node (ref "C7") (pin "1") (pinfunction "1_1") (pintype "passive"))
      (node (ref "U$1") (pin "2") (pinfunction "PA01/EINT1/SERCOM1.1_2") (pintype "bidirectional"))
      (node (ref "X4") (pin "P$2") (pinfunction "P$2_P$2") (pintype "bidirectional"))
    )
    (net (code "71") (name "VIN") (class "Default")
      (node (ref "C12") (pin "1") (pinfunction "1_1") (pintype "passive"))
      (node (ref "PC1") (pin "+") (pinfunction "+_+") (pintype "passive"))
      (node (ref "POWER") (pin "8") (pinfunction "8_8") (pintype "passive"))
      (node (ref "R1") (pin "1") (pinfunction "1_1") (pintype "passive"))
      (node (ref "T2") (pin "1") (pinfunction "D_1") (pintype "passive"))
      (node (ref "U1") (pin "3") (pinfunction "IN_3") (pintype "input"))
    )
    (net (code "72") (name "unconnected-(ECC1-NC1-Pad1)") (class "Default")
      (node (ref "ECC1") (pin "1") (pinfunction "NC1_1") (pintype "bidirectional"))
    )
    (net (code "73") (name "unconnected-(ECC1-NC2-Pad2)") (class "Default")
      (node (ref "ECC1") (pin "2") (pinfunction "NC2_2") (pintype "no_connect"))
    )
    (net (code "74") (name "unconnected-(ECC1-NC3-Pad3)") (class "Default")
      (node (ref "ECC1") (pin "3") (pinfunction "NC3_3") (pintype "no_connect"))
    )
    (net (code "75") (name "unconnected-(ECC1-NC7-Pad7)") (class "Default")
      (node (ref "ECC1") (pin "7") (pinfunction "NC7_7") (pintype "no_connect"))
    )
    (net (code "76") (name "unconnected-(LED1-DO-Pad3)") (class "Default")
      (node (ref "LED1") (pin "3") (pinfunction "DO_3") (pintype "output"))
    )
    (net (code "77") (name "unconnected-(POWER-Pad1)") (class "Default")
      (node (ref "POWER") (pin "1") (pinfunction "1_1") (pintype "passive"))
    )
    (net (code "78") (name "unconnected-(R1D-1-Pad4)") (class "Default")
      (node (ref "R1") (pin "4") (pinfunction "1_4") (pintype "passive"))
    )
    (net (code "79") (name "unconnected-(R1D-2-Pad5)") (class "Default")
      (node (ref "R1") (pin "5") (pinfunction "2_5") (pintype "passive"))
    )
    (net (code "80") (name "unconnected-(SW1-S-PadC)") (class "Default")
      (node (ref "SW1") (pin "C") (pinfunction "S_C") (pintype "passive"))
    )
    (net (code "81") (name "unconnected-(U$1B-PB31{slash}I15{slash}SERCOM5.0-Pad60)") (class "Default")
      (node (ref "U$1") (pin "60") (pinfunction "PB31/I15/SERCOM5.0_60") (pintype "bidirectional"))
    )
    (net (code "82") (name "unconnected-(U2-NC{slash}FB-Pad4)") (class "Default")
      (node (ref "U2") (pin "4") (pinfunction "NC/FB_4") (pintype "passive"))
    )
    (net (code "83") (name "unconnected-(X2-GNDDETECT-Pad9)") (class "Default")
      (node (ref "X2") (pin "9") (pinfunction "GNDDETECT_9") (pintype "bidirectional"))
    )
    (net (code "84") (name "unconnected-(X2-KEY-Pad7)") (class "Default")
      (node (ref "X2") (pin "7") (pinfunction "KEY_7") (pintype "bidirectional"))
    )
    (net (code "85") (name "unconnected-(X2-TDI-Pad8)") (class "Default")
      (node (ref "X2") (pin "8") (pinfunction "TDI_8") (pintype "bidirectional"))
    )
    (net (code "86") (name "unconnected-(X6-CLK-Pad20)") (class "Default")
      (node (ref "X6") (pin "20") (pinfunction "CLK_20") (pintype "bidirectional"))
    )
    (net (code "87") (name "unconnected-(X6-CMD-Pad19)") (class "Default")
      (node (ref "X6") (pin "19") (pinfunction "CMD_19") (pintype "bidirectional"))
    )
    (net (code "88") (name "unconnected-(X6-I34{slash}A1_6-Pad6)") (class "Default")
      (node (ref "X6") (pin "6") (pinfunction "I34/A1_6_6") (pintype "bidirectional"))
    )
    (net (code "89") (name "unconnected-(X6-I35{slash}A1_7-Pad7)") (class "Default")
      (node (ref "X6") (pin "7") (pinfunction "I35/A1_7_7") (pintype "bidirectional"))
    )
    (net (code "90") (name "unconnected-(X6-IO2{slash}A2_2-Pad24)") (class "Default")
      (node (ref "X6") (pin "24") (pinfunction "IO2/A2_2_24") (pintype "bidirectional"))
    )
    (net (code "91") (name "unconnected-(X6-IO4{slash}A2_0-Pad26)") (class "Default")
      (node (ref "X6") (pin "26") (pinfunction "IO4/A2_0_26") (pintype "bidirectional"))
    )
    (net (code "92") (name "unconnected-(X6-IO12{slash}A2_5-Pad14)") (class "Default")
      (node (ref "X6") (pin "14") (pinfunction "IO12/A2_5_14") (pintype "bidirectional"))
    )
    (net (code "93") (name "unconnected-(X6-IO13{slash}A2_4-Pad16)") (class "Default")
      (node (ref "X6") (pin "16") (pinfunction "IO13/A2_4_16") (pintype "bidirectional"))
    )
    (net (code "94") (name "unconnected-(X6-IO15{slash}A2_3-Pad23)") (class "Default")
      (node (ref "X6") (pin "23") (pinfunction "IO15/A2_3_23") (pintype "bidirectional"))
    )
    (net (code "95") (name "unconnected-(X6-IO16-Pad27)") (class "Default")
      (node (ref "X6") (pin "27") (pinfunction "IO16_27") (pintype "bidirectional"))
    )
    (net (code "96") (name "unconnected-(X6-IO17-Pad28)") (class "Default")
      (node (ref "X6") (pin "28") (pinfunction "IO17_28") (pintype "bidirectional"))
    )
    (net (code "97") (name "unconnected-(X6-IO21-Pad33)") (class "Default")
      (node (ref "X6") (pin "33") (pinfunction "IO21_33") (pintype "bidirectional"))
    )
    (net (code "98") (name "unconnected-(X6-IO22-Pad36)") (class "Default")
      (node (ref "X6") (pin "36") (pinfunction "IO22_36") (pintype "bidirectional"))
    )
    (net (code "99") (name "unconnected-(X6-IO25{slash}DAC1{slash}A2_8-Pad10)") (class "Default")
      (node (ref "X6") (pin "10") (pinfunction "IO25/DAC1/A2_8_10") (pintype "bidirectional"))
    )
    (net (code "100") (name "unconnected-(X6-IO26{slash}DAC2{slash}A2_9-Pad11)") (class "Default")
      (node (ref "X6") (pin "11") (pinfunction "IO26/DAC2/A2_9_11") (pintype "bidirectional"))
    )
    (net (code "101") (name "unconnected-(X6-IO27{slash}A2_7-Pad12)") (class "Default")
      (node (ref "X6") (pin "12") (pinfunction "IO27/A2_7_12") (pintype "bidirectional"))
    )
    (net (code "102") (name "unconnected-(X6-IO32{slash}A1_4{slash}X32P-Pad8)") (class "Default")
      (node (ref "X6") (pin "8") (pinfunction "IO32/A1_4/X32P_8") (pintype "bidirectional"))
    )
    (net (code "103") (name "unconnected-(X6-IO36{slash}SEN_VP{slash}A1_0-Pad4)") (class "Default")
      (node (ref "X6") (pin "4") (pinfunction "IO36/SEN_VP/A1_0_4") (pintype "passive"))
    )
    (net (code "104") (name "unconnected-(X6-IO39{slash}SEN_VN{slash}A1_3-Pad5)") (class "Default")
      (node (ref "X6") (pin "5") (pinfunction "IO39/SEN_VN/A1_3_5") (pintype "passive"))
    )
    (net (code "105") (name "unconnected-(X6-SD0-Pad21)") (class "Default")
      (node (ref "X6") (pin "21") (pinfunction "SD0_21") (pintype "bidirectional"))
    )
    (net (code "106") (name "unconnected-(X6-SD1-Pad22)") (class "Default")
      (node (ref "X6") (pin "22") (pinfunction "SD1_22") (pintype "bidirectional"))
    )
    (net (code "107") (name "unconnected-(X6-SD2-Pad17)") (class "Default")
      (node (ref "X6") (pin "17") (pinfunction "SD2_17") (pintype "bidirectional"))
    )
    (net (code "108") (name "unconnected-(X6-SD3-Pad18)") (class "Default")
      (node (ref "X6") (pin "18") (pinfunction "SD3_18") (pintype "bidirectional"))
    )
  )
)
